# Irrigation_Shield_v3.net
KiCad netlist of a schematic drawn in EAGLE
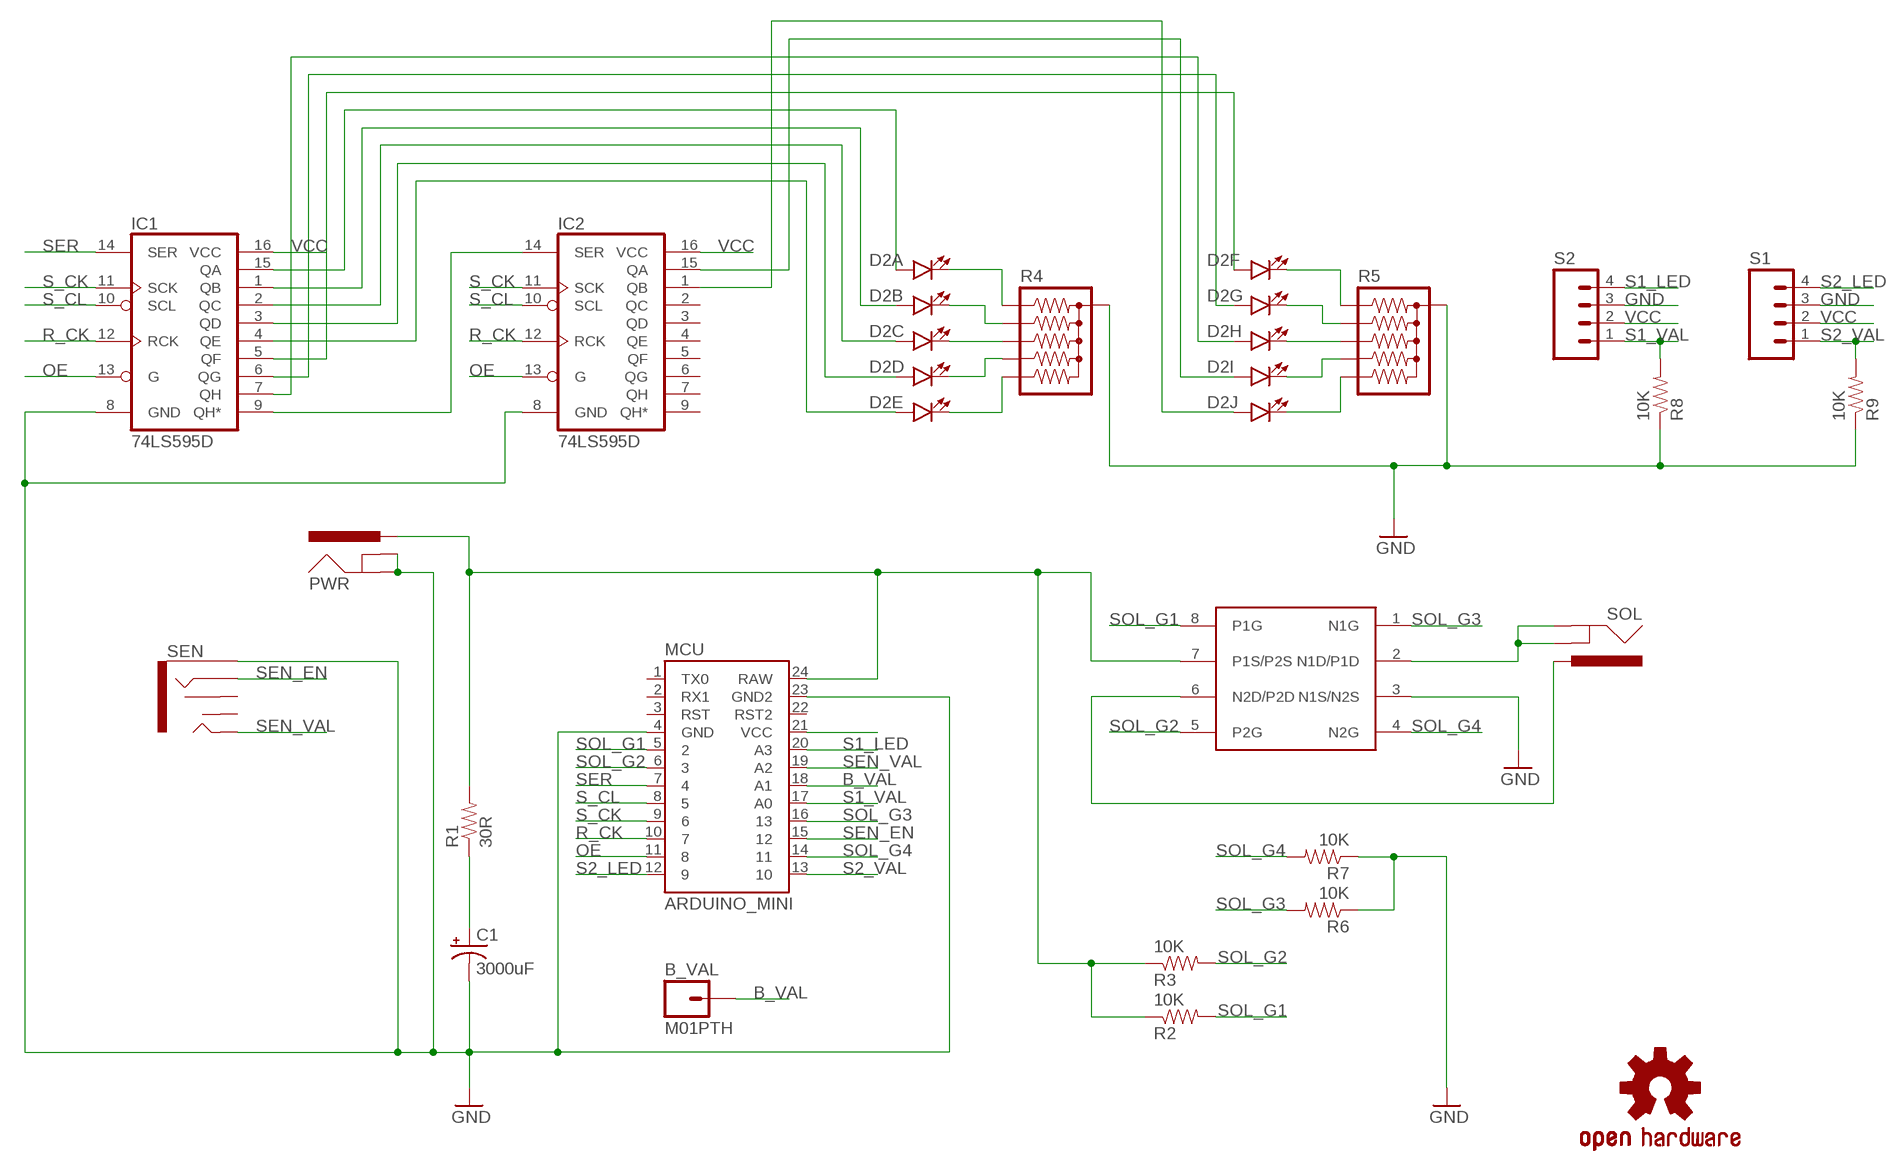
[diagram p0: schematic, sheet 1]

(export (version "E")
  (design (tool "Eeschema 10.0.6"))
  (components
    (comp (ref "B_VAL")
      (value "M01PTH")
      (footprint "eagle-import:1X01")
      (libsource (lib "eagle-import") (part "M01PTH"))
    )
    (comp (ref "C1")
      (value "3000uF")
      (footprint "eagle-import:CPOL-RADIAL-1000UF-63V")
      (libsource (lib "eagle-import") (part "CAP_POLPTH3"))
    )
    (comp (ref "D2")
      (value "LED_BARGRAPH_10")
      (footprint "eagle-import:LED_BARGAPH_10")
      (libsource (lib "eagle-import") (part "LED_BARGRAPH_10"))
    )
    (comp (ref "IC1")
      (value "74LS595D")
      (footprint "eagle-import:SO16")
      (libsource (lib "eagle-import") (part "74595DLS"))
    )
    (comp (ref "IC2")
      (value "74LS595D")
      (footprint "eagle-import:SO16")
      (libsource (lib "eagle-import") (part "74595DLS"))
    )
    (comp (ref "LOGO1")
      (value "OSHW-LOGOL")
      (footprint "eagle-import:OSHW-LOGO-L")
      (libsource (lib "eagle-import") (part "OSHW-LOGOL"))
    )
    (comp (ref "MCU")
      (value "ARDUINO_MINI")
      (footprint "eagle-import:ARDUINO_MINI")
      (libsource (lib "eagle-import") (part "ARDUINO_MINI"))
    )
    (comp (ref "PWR")
      (value "POWER_JACKPTH")
      (footprint "eagle-import:POWER_JACK_PTH")
      (libsource (lib "eagle-import") (part "SparkFun-Connectors_POWER_JACKPTH"))
    )
    (comp (ref "R1")
      (value "30R")
      (footprint "eagle-import:0603-RES")
      (libsource (lib "eagle-import") (part "RESISTOR0603-RES"))
    )
    (comp (ref "R2")
      (value "10K")
      (footprint "eagle-import:0603-RES")
      (libsource (lib "eagle-import") (part "RESISTOR0603-RES"))
    )
    (comp (ref "R3")
      (value "10K")
      (footprint "eagle-import:0603-RES")
      (libsource (lib "eagle-import") (part "RESISTOR0603-RES"))
    )
    (comp (ref "R4")
      (value "RPACK-BUSSED-SIP-PTH-5")
      (footprint "eagle-import:RPACK-SIP-PTH-5")
      (libsource (lib "eagle-import") (part "RPACK-BUSSED-SIP-PTH-5"))
    )
    (comp (ref "R5")
      (value "RPACK-BUSSED-SIP-PTH-5")
      (footprint "eagle-import:RPACK-SIP-PTH-5")
      (libsource (lib "eagle-import") (part "RPACK-BUSSED-SIP-PTH-5"))
    )
    (comp (ref "R6")
      (value "10K")
      (footprint "eagle-import:0603-RES")
      (libsource (lib "eagle-import") (part "RESISTOR0603-RES"))
    )
    (comp (ref "R7")
      (value "10K")
      (footprint "eagle-import:0603-RES")
      (libsource (lib "eagle-import") (part "RESISTOR0603-RES"))
    )
    (comp (ref "R8")
      (value "10K")
      (footprint "eagle-import:0603-RES")
      (libsource (lib "eagle-import") (part "RESISTOR0603-RES"))
    )
    (comp (ref "R9")
      (value "10K")
      (footprint "eagle-import:0603-RES")
      (libsource (lib "eagle-import") (part "RESISTOR0603-RES"))
    )
    (comp (ref "S1")
      (value "M04PTH")
      (footprint "eagle-import:1X04")
      (libsource (lib "eagle-import") (part "M04PTH"))
    )
    (comp (ref "S2")
      (value "M04PTH")
      (footprint "eagle-import:1X04")
      (libsource (lib "eagle-import") (part "M04PTH"))
    )
    (comp (ref "SEN")
      (value "AUDIO-JACK2PTH")
      (footprint "eagle-import:AUDIO-JACK")
      (libsource (lib "eagle-import") (part "AUDIO-JACK2PTH"))
    )
    (comp (ref "SOL")
      (value "POWER_JACKPTH")
      (footprint "eagle-import:POWER_JACK_PTH")
      (libsource (lib "eagle-import") (part "POWER_JACKPTH"))
    )
    (comp (ref "U$1")
      (value "ZXMHC6A07N8")
      (footprint "eagle-import:SO8")
      (libsource (lib "eagle-import") (part "ZXMHC6A07N8"))
    )
  )
  (nets
    (net (code "1") (name "/B_VAL") (class "Default")
      (node (ref "B_VAL") (pin "1") (pinfunction "1_1") (pintype "passive"))
      (node (ref "MCU") (pin "18") (pinfunction "A1_18") (pintype "bidirectional"))
    )
    (net (code "2") (name "/OE") (class "Default")
      (node (ref "IC1") (pin "13") (pinfunction "G_13") (pintype "input"))
      (node (ref "IC2") (pin "13") (pinfunction "G_13") (pintype "input"))
      (node (ref "MCU") (pin "11") (pinfunction "8_11") (pintype "bidirectional"))
    )
    (net (code "3") (name "/R_CK") (class "Default")
      (node (ref "IC1") (pin "12") (pinfunction "RCK_12") (pintype "input"))
      (node (ref "IC2") (pin "12") (pinfunction "RCK_12") (pintype "input"))
      (node (ref "MCU") (pin "10") (pinfunction "7_10") (pintype "bidirectional"))
    )
    (net (code "4") (name "/S1_LED") (class "Default")
      (node (ref "MCU") (pin "20") (pinfunction "A3_20") (pintype "bidirectional"))
      (node (ref "S2") (pin "4") (pinfunction "4_4") (pintype "passive"))
    )
    (net (code "5") (name "/S1_VAL") (class "Default")
      (node (ref "MCU") (pin "17") (pinfunction "A0_17") (pintype "bidirectional"))
      (node (ref "R8") (pin "2") (pinfunction "2_2") (pintype "passive"))
      (node (ref "S2") (pin "1") (pinfunction "1_1") (pintype "passive"))
    )
    (net (code "6") (name "/S2_LED") (class "Default")
      (node (ref "MCU") (pin "12") (pinfunction "9_12") (pintype "bidirectional"))
      (node (ref "S1") (pin "4") (pinfunction "4_4") (pintype "passive"))
    )
    (net (code "7") (name "/S2_VAL") (class "Default")
      (node (ref "MCU") (pin "13") (pinfunction "10_13") (pintype "bidirectional"))
      (node (ref "R9") (pin "2") (pinfunction "2_2") (pintype "passive"))
      (node (ref "S1") (pin "1") (pinfunction "1_1") (pintype "passive"))
    )
    (net (code "8") (name "/SEN_EN") (class "Default")
      (node (ref "MCU") (pin "15") (pinfunction "12_15") (pintype "bidirectional"))
      (node (ref "SEN") (pin "RING") (pinfunction "RING_RING") (pintype "bidirectional"))
    )
    (net (code "9") (name "/SEN_VAL") (class "Default")
      (node (ref "MCU") (pin "19") (pinfunction "A2_19") (pintype "bidirectional"))
      (node (ref "SEN") (pin "TIP") (pinfunction "TIP_TIP") (pintype "bidirectional"))
    )
    (net (code "10") (name "/SER") (class "Default")
      (node (ref "IC1") (pin "14") (pinfunction "SER_14") (pintype "input"))
      (node (ref "MCU") (pin "7") (pinfunction "4_7") (pintype "bidirectional"))
    )
    (net (code "11") (name "/SOL_G1") (class "Default")
      (node (ref "MCU") (pin "5") (pinfunction "2_5") (pintype "bidirectional"))
      (node (ref "R2") (pin "2") (pinfunction "2_2") (pintype "passive"))
      (node (ref "U$1") (pin "8") (pinfunction "P1G_8") (pintype "bidirectional"))
    )
    (net (code "12") (name "/SOL_G2") (class "Default")
      (node (ref "MCU") (pin "6") (pinfunction "3_6") (pintype "bidirectional"))
      (node (ref "R3") (pin "2") (pinfunction "2_2") (pintype "passive"))
      (node (ref "U$1") (pin "5") (pinfunction "P2G_5") (pintype "bidirectional"))
    )
    (net (code "13") (name "/SOL_G3") (class "Default")
      (node (ref "MCU") (pin "16") (pinfunction "13_16") (pintype "bidirectional"))
      (node (ref "R6") (pin "2") (pinfunction "2_2") (pintype "passive"))
      (node (ref "U$1") (pin "1") (pinfunction "N1G_1") (pintype "bidirectional"))
    )
    (net (code "14") (name "/SOL_G4") (class "Default")
      (node (ref "MCU") (pin "14") (pinfunction "11_14") (pintype "bidirectional"))
      (node (ref "R7") (pin "2") (pinfunction "2_2") (pintype "passive"))
      (node (ref "U$1") (pin "4") (pinfunction "N2G_4") (pintype "bidirectional"))
    )
    (net (code "15") (name "/S_CK") (class "Default")
      (node (ref "IC1") (pin "11") (pinfunction "SCK_11") (pintype "input"))
      (node (ref "IC2") (pin "11") (pinfunction "SCK_11") (pintype "input"))
      (node (ref "MCU") (pin "9") (pinfunction "6_9") (pintype "bidirectional"))
    )
    (net (code "16") (name "/S_CL") (class "Default")
      (node (ref "IC1") (pin "10") (pinfunction "SCL_10") (pintype "input"))
      (node (ref "IC2") (pin "10") (pinfunction "SCL_10") (pintype "input"))
      (node (ref "MCU") (pin "8") (pinfunction "5_8") (pintype "bidirectional"))
    )
    (net (code "17") (name "/VCC") (class "Default")
      (node (ref "IC1") (pin "16") (pinfunction "VCC_16") (pintype "power_in"))
      (node (ref "IC2") (pin "16") (pinfunction "VCC_16") (pintype "power_in"))
      (node (ref "MCU") (pin "21") (pinfunction "VCC_21") (pintype "bidirectional"))
      (node (ref "S1") (pin "2") (pinfunction "2_2") (pintype "passive"))
      (node (ref "S2") (pin "2") (pinfunction "2_2") (pintype "passive"))
    )
    (net (code "18") (name "GND") (class "Default")
      (node (ref "C1") (pin "2") (pinfunction "-_2") (pintype "passive"))
      (node (ref "IC1") (pin "8") (pinfunction "GND_8") (pintype "power_in"))
      (node (ref "IC2") (pin "8") (pinfunction "GND_8") (pintype "power_in"))
      (node (ref "MCU") (pin "23") (pinfunction "GND2_23") (pintype "bidirectional"))
      (node (ref "MCU") (pin "4") (pinfunction "GND_4") (pintype "bidirectional"))
      (node (ref "PWR") (pin "GND") (pinfunction "GND_GND") (pintype "bidirectional"))
      (node (ref "PWR") (pin "GNDBREAK") (pinfunction "GNDBREAK_GNDBREAK") (pintype "bidirectional"))
      (node (ref "R4") (pin "P$1") (pinfunction "1_P$1") (pintype "passive"))
      (node (ref "R5") (pin "P$1") (pinfunction "1_P$1") (pintype "passive"))
      (node (ref "R6") (pin "1") (pinfunction "1_1") (pintype "passive"))
      (node (ref "R7") (pin "1") (pinfunction "1_1") (pintype "passive"))
      (node (ref "R8") (pin "1") (pinfunction "1_1") (pintype "passive"))
      (node (ref "R9") (pin "1") (pinfunction "1_1") (pintype "passive"))
      (node (ref "S1") (pin "3") (pinfunction "3_3") (pintype "passive"))
      (node (ref "S2") (pin "3") (pinfunction "3_3") (pintype "passive"))
      (node (ref "SEN") (pin "SLEEVE") (pinfunction "SLEEVE_SLEEVE") (pintype "bidirectional"))
      (node (ref "U$1") (pin "3") (pinfunction "N1S/N2S_3") (pintype "bidirectional"))
    )
    (net (code "19") (name "Net-(C1-+)") (class "Default")
      (node (ref "C1") (pin "1") (pinfunction "+_1") (pintype "passive"))
      (node (ref "R1") (pin "1") (pinfunction "1_1") (pintype "passive"))
    )
    (net (code "20") (name "Net-(D2A-A)") (class "Default")
      (node (ref "D2") (pin "1") (pinfunction "A_1") (pintype "passive"))
      (node (ref "IC1") (pin "15") (pinfunction "QA_15") (pintype "tri_state"))
    )
    (net (code "21") (name "Net-(D2A-C)") (class "Default")
      (node (ref "D2") (pin "20") (pinfunction "C_20") (pintype "passive"))
      (node (ref "R4") (pin "P$2") (pinfunction "2_P$2") (pintype "passive"))
    )
    (net (code "22") (name "Net-(D2B-A)") (class "Default")
      (node (ref "D2") (pin "2") (pinfunction "A_2") (pintype "passive"))
      (node (ref "IC1") (pin "1") (pinfunction "QB_1") (pintype "tri_state"))
    )
    (net (code "23") (name "Net-(D2B-C)") (class "Default")
      (node (ref "D2") (pin "19") (pinfunction "C_19") (pintype "passive"))
      (node (ref "R4") (pin "P$3") (pinfunction "3_P$3") (pintype "passive"))
    )
    (net (code "24") (name "Net-(D2C-A)") (class "Default")
      (node (ref "D2") (pin "3") (pinfunction "A_3") (pintype "passive"))
      (node (ref "IC1") (pin "2") (pinfunction "QC_2") (pintype "tri_state"))
    )
    (net (code "25") (name "Net-(D2C-C)") (class "Default")
      (node (ref "D2") (pin "18") (pinfunction "C_18") (pintype "passive"))
      (node (ref "R4") (pin "P$4") (pinfunction "4_P$4") (pintype "passive"))
    )
    (net (code "26") (name "Net-(D2D-A)") (class "Default")
      (node (ref "D2") (pin "4") (pinfunction "A_4") (pintype "passive"))
      (node (ref "IC1") (pin "3") (pinfunction "QD_3") (pintype "tri_state"))
    )
    (net (code "27") (name "Net-(D2D-C)") (class "Default")
      (node (ref "D2") (pin "17") (pinfunction "C_17") (pintype "passive"))
      (node (ref "R4") (pin "P$5") (pinfunction "5_P$5") (pintype "passive"))
    )
    (net (code "28") (name "Net-(D2E-A)") (class "Default")
      (node (ref "D2") (pin "5") (pinfunction "A_5") (pintype "passive"))
      (node (ref "IC1") (pin "4") (pinfunction "QE_4") (pintype "tri_state"))
    )
    (net (code "29") (name "Net-(D2E-C)") (class "Default")
      (node (ref "D2") (pin "16") (pinfunction "C_16") (pintype "passive"))
      (node (ref "R4") (pin "P$6") (pinfunction "6_P$6") (pintype "passive"))
    )
    (net (code "30") (name "Net-(D2F-A)") (class "Default")
      (node (ref "D2") (pin "6") (pinfunction "A_6") (pintype "passive"))
      (node (ref "IC1") (pin "5") (pinfunction "QF_5") (pintype "tri_state"))
    )
    (net (code "31") (name "Net-(D2F-C)") (class "Default")
      (node (ref "D2") (pin "15") (pinfunction "C_15") (pintype "passive"))
      (node (ref "R5") (pin "P$2") (pinfunction "2_P$2") (pintype "passive"))
    )
    (net (code "32") (name "Net-(D2G-A)") (class "Default")
      (node (ref "D2") (pin "7") (pinfunction "A_7") (pintype "passive"))
      (node (ref "IC1") (pin "6") (pinfunction "QG_6") (pintype "tri_state"))
    )
    (net (code "33") (name "Net-(D2G-C)") (class "Default")
      (node (ref "D2") (pin "14") (pinfunction "C_14") (pintype "passive"))
      (node (ref "R5") (pin "P$3") (pinfunction "3_P$3") (pintype "passive"))
    )
    (net (code "34") (name "Net-(D2H-A)") (class "Default")
      (node (ref "D2") (pin "8") (pinfunction "A_8") (pintype "passive"))
      (node (ref "IC1") (pin "7") (pinfunction "QH_7") (pintype "tri_state"))
    )
    (net (code "35") (name "Net-(D2H-C)") (class "Default")
      (node (ref "D2") (pin "13") (pinfunction "C_13") (pintype "passive"))
      (node (ref "R5") (pin "P$4") (pinfunction "4_P$4") (pintype "passive"))
    )
    (net (code "36") (name "Net-(D2I-A)") (class "Default")
      (node (ref "D2") (pin "9") (pinfunction "A_9") (pintype "passive"))
      (node (ref "IC2") (pin "15") (pinfunction "QA_15") (pintype "tri_state"))
    )
    (net (code "37") (name "Net-(D2I-C)") (class "Default")
      (node (ref "D2") (pin "12") (pinfunction "C_12") (pintype "passive"))
      (node (ref "R5") (pin "P$5") (pinfunction "5_P$5") (pintype "passive"))
    )
    (net (code "38") (name "Net-(D2J-A)") (class "Default")
      (node (ref "D2") (pin "10") (pinfunction "A_10") (pintype "passive"))
      (node (ref "IC2") (pin "1") (pinfunction "QB_1") (pintype "tri_state"))
    )
    (net (code "39") (name "Net-(D2J-C)") (class "Default")
      (node (ref "D2") (pin "11") (pinfunction "C_11") (pintype "passive"))
      (node (ref "R5") (pin "P$6") (pinfunction "6_P$6") (pintype "passive"))
    )
    (net (code "40") (name "Net-(IC1-QH*)") (class "Default")
      (node (ref "IC1") (pin "9") (pinfunction "QH*_9") (pintype "tri_state"))
      (node (ref "IC2") (pin "14") (pinfunction "SER_14") (pintype "input"))
    )
    (net (code "41") (name "Net-(MCU-RAW)") (class "Default")
      (node (ref "MCU") (pin "24") (pinfunction "RAW_24") (pintype "bidirectional"))
      (node (ref "PWR") (pin "PWR") (pinfunction "PWR_PWR") (pintype "bidirectional"))
      (node (ref "R1") (pin "2") (pinfunction "2_2") (pintype "passive"))
      (node (ref "R2") (pin "1") (pinfunction "1_1") (pintype "passive"))
      (node (ref "R3") (pin "1") (pinfunction "1_1") (pintype "passive"))
      (node (ref "U$1") (pin "7") (pinfunction "P1S/P2S_7") (pintype "bidirectional"))
    )
    (net (code "42") (name "Net-(U$1-N1D{slash}P1D)") (class "Default")
      (node (ref "SOL") (pin "GND") (pinfunction "GND_GND") (pintype "bidirectional"))
      (node (ref "SOL") (pin "GNDBREAK") (pinfunction "GNDBREAK_GNDBREAK") (pintype "bidirectional"))
      (node (ref "U$1") (pin "2") (pinfunction "N1D/P1D_2") (pintype "bidirectional"))
    )
    (net (code "43") (name "Net-(U$1-N2D{slash}P2D)") (class "Default")
      (node (ref "SOL") (pin "PWR") (pinfunction "PWR_PWR") (pintype "bidirectional"))
      (node (ref "U$1") (pin "6") (pinfunction "N2D/P2D_6") (pintype "bidirectional"))
    )
    (net (code "44") (name "unconnected-(IC2-QC-Pad2)") (class "Default")
      (node (ref "IC2") (pin "2") (pinfunction "QC_2") (pintype "tri_state"))
    )
    (net (code "45") (name "unconnected-(IC2-QD-Pad3)") (class "Default")
      (node (ref "IC2") (pin "3") (pinfunction "QD_3") (pintype "tri_state"))
    )
    (net (code "46") (name "unconnected-(IC2-QE-Pad4)") (class "Default")
      (node (ref "IC2") (pin "4") (pinfunction "QE_4") (pintype "tri_state"))
    )
    (net (code "47") (name "unconnected-(IC2-QF-Pad5)") (class "Default")
      (node (ref "IC2") (pin "5") (pinfunction "QF_5") (pintype "tri_state"))
    )
    (net (code "48") (name "unconnected-(IC2-QG-Pad6)") (class "Default")
      (node (ref "IC2") (pin "6") (pinfunction "QG_6") (pintype "tri_state"))
    )
    (net (code "49") (name "unconnected-(IC2-QH*-Pad9)") (class "Default")
      (node (ref "IC2") (pin "9") (pinfunction "QH*_9") (pintype "tri_state"))
    )
    (net (code "50") (name "unconnected-(IC2-QH-Pad7)") (class "Default")
      (node (ref "IC2") (pin "7") (pinfunction "QH_7") (pintype "tri_state"))
    )
    (net (code "51") (name "unconnected-(MCU-RST-Pad3)") (class "Default")
      (node (ref "MCU") (pin "3") (pinfunction "RST_3") (pintype "bidirectional"))
    )
    (net (code "52") (name "unconnected-(MCU-RST2-Pad22)") (class "Default")
      (node (ref "MCU") (pin "22") (pinfunction "RST2_22") (pintype "bidirectional"))
    )
    (net (code "53") (name "unconnected-(MCU-RX1-Pad2)") (class "Default")
      (node (ref "MCU") (pin "2") (pinfunction "RX1_2") (pintype "bidirectional"))
    )
    (net (code "54") (name "unconnected-(MCU-TX0-Pad1)") (class "Default")
      (node (ref "MCU") (pin "1") (pinfunction "TX0_1") (pintype "bidirectional"))
    )
    (net (code "55") (name "unconnected-(SEN-PadRSH)") (class "Default")
      (node (ref "SEN") (pin "RSH") (pinfunction "RSH_RSH") (pintype "bidirectional"))
    )
    (net (code "56") (name "unconnected-(SEN-PadTSH)") (class "Default")
      (node (ref "SEN") (pin "TSH") (pinfunction "TSH_TSH") (pintype "bidirectional"))
    )
  )
)
